# BQ76952_AFE.net
KiCad netlist of a schematic drawn in Altium Designer
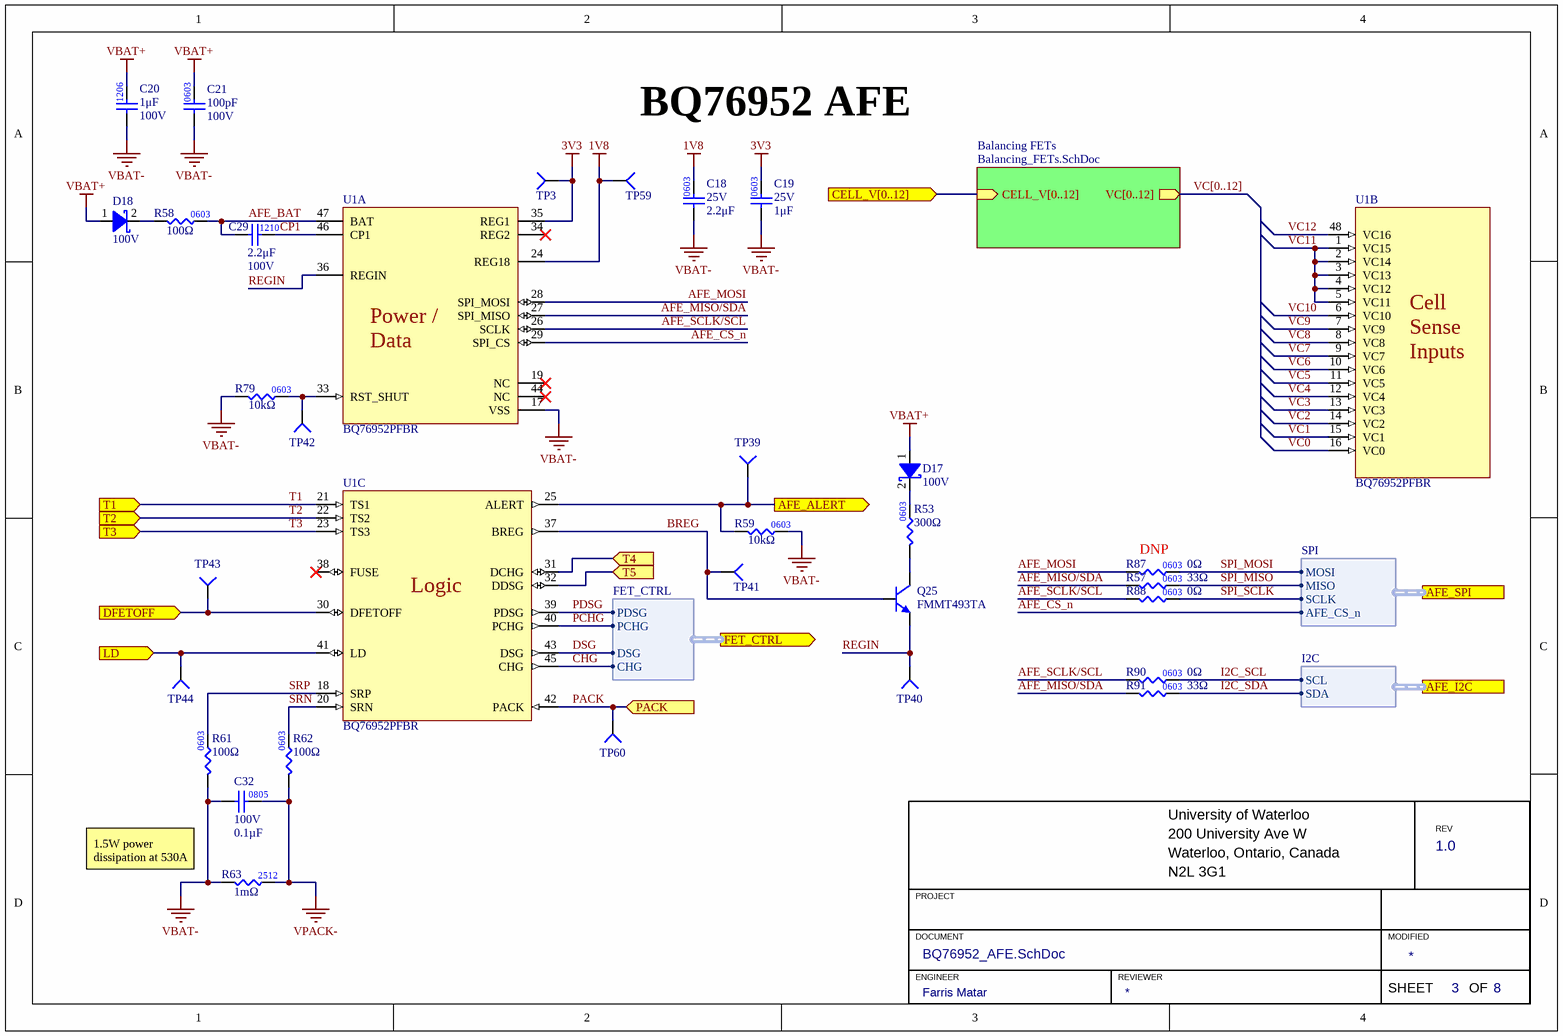
[diagram p0: BQ76952_AFE.SchDoc]

(export (version "E")
  (design (tool "Eeschema 10.0.6"))
  (components
    (comp (ref "C18")
      (value "2.2μF")
      (footprint "CAP0603")
      (description "CAP CER 2.2UF 25V X5R 0603")
      (fields (field (name "VOLTAGE RATING") "25V") (field (name "Comment") "CAP_2.2uF_25V_0603"))
      (libsource (lib "Personal_Schematic_Library_2022") (part "CAP_2.2uF_25V_0603"))
    )
    (comp (ref "C19")
      (value "1μF")
      (footprint "CAP0603")
      (description "CAP CER 1UF 25V X5R 0603")
      (fields (field (name "VOLTAGE RATING") "25V") (field (name "Comment") "CAP_1uF_25V_0603"))
      (libsource (lib "Personal_Schematic_Library_2022") (part "CAP_1uF_25V_0603"))
    )
    (comp (ref "C20")
      (value "1μF")
      (footprint "CAP1206")
      (description "CAP CER 1UF 100V X7R 1206")
      (fields (field (name "VOLTAGE RATING") "100V") (field (name "Comment") "CAP_1uF_100V_1206"))
      (libsource (lib "Personal_Schematic_Library_2022") (part "CAP_1uF_100V_1206"))
    )
    (comp (ref "C21")
      (value "100pF")
      (footprint "CAP2012")
      (description "CAP CER 100PF 100V X7R 0603")
      (fields (field (name "VOLTAGE RATING") "100V") (field (name "Comment") "CAP_100pF_100V_0603"))
      (libsource (lib "Personal_Schematic_Library_2022") (part "CAP_100pF_100V_0603"))
    )
    (comp (ref "C29")
      (value "2.2μF")
      (footprint "CAP1210")
      (description "CAP CER 2.2UF 100V X7R 1210")
      (fields (field (name "VOLTAGE RATING") "100V") (field (name "Comment") "CAP_2.2uF_100V_1210"))
      (libsource (lib "Personal_Schematic_Library_2022") (part "CAP_2.2uF_100V_1210"))
    )
    (comp (ref "C32")
      (value "0.1µF")
      (footprint "CAP0805")
      (description "CAP CER 0.1UF 100V X7R 0805")
      (fields (field (name "VOLTAGE RATING") "100V") (field (name "Comment") "CAP_0.1uF_100V_0805"))
      (libsource (lib "Personal_Schematic_Library_2022") (part "CAP_0.1uF_100V_0805"))
    )
    (comp (ref "D17")
      (value "DIO_SCHOTTKY_100V_1A")
      (footprint "SOD-123_FLAT")
      (description "DIODE SCHOTTKY 100V 1A SOD-123F")
      (fields (field (name "VR (MAX)") "100V"))
      (libsource (lib "Personal_Schematic_Library_2022") (part "DIO_SCHOTTKY_100V_1A"))
    )
    (comp (ref "D18")
      (value "DIO_SCHOTTKY_100V_1A")
      (footprint "SOD-123_FLAT")
      (description "DIODE SCHOTTKY 100V 1A SOD-123F")
      (fields (field (name "VR (MAX)") "100V"))
      (libsource (lib "Personal_Schematic_Library_2022") (part "DIO_SCHOTTKY_100V_1A"))
    )
    (comp (ref "Q25")
      (value "NPN_100V_1A")
      (footprint "SOT23-3")
      (description "TRANS NPN 100V 1A SOT23-3")
      (fields (field (name "MANUFACTURER PART NUMBER 1") "FMMT493TA"))
      (libsource (lib "Personal_Schematic_Library_2022") (part "NPN_100V_1A"))
    )
    (comp (ref "R53")
      (value "300Ω")
      (footprint "RES0603")
      (description "RES 200 OHM 1% 1/10W 0603")
      (fields (field (name "TOLERANCE") "1%") (field (name "Comment") "RES_300Ω_0603_1%"))
      (libsource (lib "Personal_Schematic_Library_2022") (part "RES_300Ω_0603_1%"))
    )
    (comp (ref "R57")
      (value "33Ω")
      (footprint "RES0603")
      (description "RES 33 OHM 1% 1/10W 0603")
      (fields (field (name "Comment") "RES_33Ω_0603_1%"))
      (libsource (lib "Personal_Schematic_Library_2022") (part "RES_33Ω_0603_1%"))
    )
    (comp (ref "R58")
      (value "100Ω")
      (footprint "RES0603")
      (description "RES 100 OHM 1% 1/10W 0603")
      (fields (field (name "Comment") "RES_100Ω_0603_1%"))
      (libsource (lib "Personal_Schematic_Library_2022") (part "RES_100Ω_0603_1%"))
    )
    (comp (ref "R59")
      (value "10kΩ")
      (footprint "RES0603")
      (description "RES 10K OHM 1% 1/8W 0603")
      (fields (field (name "Comment") "RES_10kΩ_0603_1%"))
      (libsource (lib "Personal_Schematic_Library_2022") (part "RES_10kΩ_0603_1%"))
    )
    (comp (ref "R61")
      (value "100Ω")
      (footprint "RES0603")
      (description "RES 100 OHM 1% 1/10W 0603")
      (fields (field (name "Comment") "RES_100Ω_0603_1%"))
      (libsource (lib "Personal_Schematic_Library_2022") (part "RES_100Ω_0603_1%"))
    )
    (comp (ref "R62")
      (value "100Ω")
      (footprint "RES0603")
      (description "RES 100 OHM 1% 1/10W 0603")
      (fields (field (name "Comment") "RES_100Ω_0603_1%"))
      (libsource (lib "Personal_Schematic_Library_2022") (part "RES_100Ω_0603_1%"))
    )
    (comp (ref "R63")
      (value "1mΩ")
      (footprint "RESC6532X75N")
      (description "RES 1 mOHM 1% 3W 2512")
      (fields (field (name "Comment") "RES_1mΩ_2512_1%"))
      (libsource (lib "Personal_Schematic_Library_2022") (part "RES_1mΩ_2512_1%"))
    )
    (comp (ref "R79")
      (value "10kΩ")
      (footprint "RES0603")
      (description "RES 10K OHM 1% 1/8W 0603")
      (fields (field (name "Comment") "RES_10kΩ_0603_1%"))
      (libsource (lib "Personal_Schematic_Library_2022") (part "RES_10kΩ_0603_1%"))
    )
    (comp (ref "R87")
      (value "0Ω")
      (footprint "RES0603")
      (description "RES 0 OHM JUMPER 1/10W 0603")
      (fields (field (name "Comment") "RES_0Ω_0603"))
      (libsource (lib "Personal_Schematic_Library_2022") (part "RES_0Ω_0603"))
    )
    (comp (ref "R88")
      (value "0Ω")
      (footprint "RES0603")
      (description "RES 0 OHM JUMPER 1/10W 0603")
      (fields (field (name "Comment") "RES_0Ω_0603"))
      (libsource (lib "Personal_Schematic_Library_2022") (part "RES_0Ω_0603"))
    )
    (comp (ref "R90")
      (value "0Ω")
      (footprint "RES0603")
      (description "RES 0 OHM JUMPER 1/10W 0603")
      (fields (field (name "Comment") "RES_0Ω_0603"))
      (libsource (lib "Personal_Schematic_Library_2022") (part "RES_0Ω_0603"))
    )
    (comp (ref "R91")
      (value "33Ω")
      (footprint "RES0603")
      (description "RES 33 OHM 1% 1/10W 0603")
      (fields (field (name "Comment") "RES_33Ω_0603_1%"))
      (libsource (lib "Personal_Schematic_Library_2022") (part "RES_33Ω_0603_1%"))
    )
    (comp (ref "TP3")
      (value "TESTPOINT_SMD_LOOP")
      (footprint "S1751-46R")
      (description "TESTPOINT SMD LOOP")
      (libsource (lib "UWRT_Schematic_Library_2020") (part "TESTPOINT_SMD_LOOP"))
    )
    (comp (ref "TP39")
      (value "TESTPOINT_1MM_CIRCLE")
      (footprint "TESTPOINT_CIRCLE_1MM")
      (description "TESTPOINT 1MM CIRCLE")
      (libsource (lib "Personal_Schematic_Library_2022") (part "TESTPOINT_1MM_CIRCLE"))
    )
    (comp (ref "TP40")
      (value "TESTPOINT_1MM_CIRCLE")
      (footprint "TESTPOINT_CIRCLE_1MM")
      (description "TESTPOINT 1MM CIRCLE")
      (libsource (lib "Personal_Schematic_Library_2022") (part "TESTPOINT_1MM_CIRCLE"))
    )
    (comp (ref "TP41")
      (value "TESTPOINT_1MM_CIRCLE")
      (footprint "TESTPOINT_CIRCLE_1MM")
      (description "TESTPOINT 1MM CIRCLE")
      (libsource (lib "Personal_Schematic_Library_2022") (part "TESTPOINT_1MM_CIRCLE"))
    )
    (comp (ref "TP42")
      (value "TESTPOINT_1MM_CIRCLE")
      (footprint "TESTPOINT_CIRCLE_1MM")
      (description "TESTPOINT 1MM CIRCLE")
      (libsource (lib "Personal_Schematic_Library_2022") (part "TESTPOINT_1MM_CIRCLE"))
    )
    (comp (ref "TP43")
      (value "TESTPOINT_1MM_CIRCLE")
      (footprint "TESTPOINT_CIRCLE_1MM")
      (description "TESTPOINT 1MM CIRCLE")
      (libsource (lib "Personal_Schematic_Library_2022") (part "TESTPOINT_1MM_CIRCLE"))
    )
    (comp (ref "TP44")
      (value "TESTPOINT_1MM_CIRCLE")
      (footprint "TESTPOINT_CIRCLE_1MM")
      (description "TESTPOINT 1MM CIRCLE")
      (libsource (lib "Personal_Schematic_Library_2022") (part "TESTPOINT_1MM_CIRCLE"))
    )
    (comp (ref "TP59")
      (value "TESTPOINT_1MM_SQUARE")
      (footprint "TESTPOINT_SQUARE_1MM")
      (description "TESTPOINT 1MM SQUARE")
      (libsource (lib "Personal_Schematic_Library_2022") (part "TESTPOINT_1MM_SQUARE"))
    )
    (comp (ref "TP60")
      (value "TESTPOINT_1MM_CIRCLE")
      (footprint "TESTPOINT_CIRCLE_1MM")
      (description "TESTPOINT 1MM CIRCLE")
      (libsource (lib "Personal_Schematic_Library_2022") (part "TESTPOINT_1MM_CIRCLE"))
    )
    (comp (ref "U1")
      (value "BQ76952PFBR")
      (footprint "TI_48-TQFP")
      (description "IC BAT LIFEPO4/LI-ION 3-16C TQFP")
      (libsource (lib "Personal_Schematic_Library_2022") (part "BQ7695204PFBR"))
    )
  )
  (nets
    (net (code "17") (name "/AFE_ALERT") (class "Default")
      (node (ref "R59") (pin "1") (pinfunction "1_1") (pintype "passive"))
      (node (ref "TP39") (pin "1") (pinfunction "=value_1") (pintype "passive"))
      (node (ref "U1") (pin "25") (pinfunction "ALERT_25") (pintype "output"))
    )
    (net (code "18") (name "/AFE_BAT") (class "Default")
      (node (ref "C29") (pin "1") (pinfunction "1_1") (pintype "passive"))
      (node (ref "R58") (pin "2") (pinfunction "2_2") (pintype "passive"))
      (node (ref "U1") (pin "47") (pinfunction "BAT_47") (pintype "power_in"))
    )
    (net (code "19") (name "/AFE_CS_n") (class "Default")
      (node (ref "U1") (pin "29") (pinfunction "SPI_CS_29") (pintype "bidirectional"))
    )
    (net (code "20") (name "/AFE_MISO{slash}SDA") (class "Default")
      (node (ref "R57") (pin "1") (pinfunction "1_1") (pintype "passive"))
      (node (ref "R91") (pin "1") (pinfunction "1_1") (pintype "passive"))
      (node (ref "U1") (pin "27") (pinfunction "SPI_MISO_27") (pintype "bidirectional"))
    )
    (net (code "21") (name "/AFE_MOSI") (class "Default")
      (node (ref "R87") (pin "1") (pinfunction "1_1") (pintype "passive"))
      (node (ref "U1") (pin "28") (pinfunction "SPI_MOSI_28") (pintype "bidirectional"))
    )
    (net (code "22") (name "/AFE_SCLK{slash}SCL") (class "Default")
      (node (ref "R88") (pin "1") (pinfunction "1_1") (pintype "passive"))
      (node (ref "R90") (pin "1") (pinfunction "1_1") (pintype "passive"))
      (node (ref "U1") (pin "26") (pinfunction "SCLK_26") (pintype "bidirectional"))
    )
    (net (code "23") (name "/BREG") (class "Default")
      (node (ref "Q25") (pin "1") (pinfunction "B_1") (pintype "passive"))
      (node (ref "TP41") (pin "1") (pinfunction "=value_1") (pintype "passive"))
      (node (ref "U1") (pin "37") (pinfunction "BREG_37") (pintype "output"))
    )
    (net (code "25") (name "/CHG") (class "Default")
      (node (ref "U1") (pin "45") (pinfunction "CHG_45") (pintype "output"))
    )
    (net (code "26") (name "/CP1") (class "Default")
      (node (ref "C29") (pin "2") (pinfunction "2_2") (pintype "passive"))
      (node (ref "U1") (pin "46") (pinfunction "CP1_46") (pintype "power_in"))
    )
    (net (code "27") (name "/DFETOFF") (class "Default")
      (node (ref "TP43") (pin "1") (pinfunction "=value_1") (pintype "passive"))
      (node (ref "U1") (pin "30") (pinfunction "DFETOFF_30") (pintype "bidirectional"))
    )
    (net (code "28") (name "/DSG") (class "Default")
      (node (ref "U1") (pin "43") (pinfunction "DSG_43") (pintype "output"))
    )
    (net (code "29") (name "/I2C_SCL") (class "Default")
      (node (ref "R90") (pin "2") (pinfunction "2_2") (pintype "passive"))
    )
    (net (code "30") (name "/I2C_SDA") (class "Default")
      (node (ref "R91") (pin "2") (pinfunction "2_2") (pintype "passive"))
    )
    (net (code "31") (name "/LD") (class "Default")
      (node (ref "TP44") (pin "1") (pinfunction "=value_1") (pintype "passive"))
      (node (ref "U1") (pin "41") (pinfunction "LD_41") (pintype "bidirectional"))
    )
    (net (code "32") (name "/PACK") (class "Default")
      (node (ref "TP60") (pin "1") (pinfunction "=value_1") (pintype "passive"))
      (node (ref "U1") (pin "42") (pinfunction "PACK_42") (pintype "input"))
    )
    (net (code "33") (name "/PCHG") (class "Default")
      (node (ref "U1") (pin "40") (pinfunction "PCHG_40") (pintype "output"))
    )
    (net (code "34") (name "/PDSG") (class "Default")
      (node (ref "U1") (pin "39") (pinfunction "PDSG_39") (pintype "output"))
    )
    (net (code "35") (name "/REGIN") (class "Default")
      (node (ref "Q25") (pin "2") (pinfunction "E_2") (pintype "passive"))
      (node (ref "TP40") (pin "1") (pinfunction "=value_1") (pintype "passive"))
      (node (ref "U1") (pin "36") (pinfunction "REGIN_36") (pintype "power_in"))
    )
    (net (code "36") (name "/SPI_MISO") (class "Default")
      (node (ref "R57") (pin "2") (pinfunction "2_2") (pintype "passive"))
    )
    (net (code "37") (name "/SPI_MOSI") (class "Default")
      (node (ref "R87") (pin "2") (pinfunction "2_2") (pintype "passive"))
    )
    (net (code "38") (name "/SPI_SCLK") (class "Default")
      (node (ref "R88") (pin "2") (pinfunction "2_2") (pintype "passive"))
    )
    (net (code "39") (name "/SRN") (class "Default")
      (node (ref "R62") (pin "2") (pinfunction "2_2") (pintype "passive"))
      (node (ref "U1") (pin "20") (pinfunction "SRN_20") (pintype "input"))
    )
    (net (code "40") (name "/SRP") (class "Default")
      (node (ref "R61") (pin "2") (pinfunction "2_2") (pintype "passive"))
      (node (ref "U1") (pin "18") (pinfunction "SRP_18") (pintype "input"))
    )
    (net (code "41") (name "/T1") (class "Default")
      (node (ref "U1") (pin "21") (pinfunction "TS1_21") (pintype "input"))
    )
    (net (code "42") (name "/T2") (class "Default")
      (node (ref "U1") (pin "22") (pinfunction "TS2_22") (pintype "input"))
    )
    (net (code "43") (name "/T3") (class "Default")
      (node (ref "U1") (pin "23") (pinfunction "TS3_23") (pintype "input"))
    )
    (net (code "44") (name "/T4") (class "Default")
      (node (ref "U1") (pin "31") (pinfunction "DCHG_31") (pintype "bidirectional"))
    )
    (net (code "45") (name "/T5") (class "Default")
      (node (ref "U1") (pin "32") (pinfunction "DDSG_32") (pintype "bidirectional"))
    )
    (net (code "46") (name "/VC0") (class "Default")
      (node (ref "U1") (pin "16") (pinfunction "VC0_16") (pintype "input"))
    )
    (net (code "47") (name "/VC1") (class "Default")
      (node (ref "U1") (pin "15") (pinfunction "VC1_15") (pintype "input"))
    )
    (net (code "48") (name "/VC2") (class "Default")
      (node (ref "U1") (pin "14") (pinfunction "VC2_14") (pintype "input"))
    )
    (net (code "49") (name "/VC3") (class "Default")
      (node (ref "U1") (pin "13") (pinfunction "VC3_13") (pintype "input"))
    )
    (net (code "50") (name "/VC4") (class "Default")
      (node (ref "U1") (pin "12") (pinfunction "VC4_12") (pintype "input"))
    )
    (net (code "51") (name "/VC5") (class "Default")
      (node (ref "U1") (pin "11") (pinfunction "VC5_11") (pintype "input"))
    )
    (net (code "52") (name "/VC6") (class "Default")
      (node (ref "U1") (pin "10") (pinfunction "VC6_10") (pintype "input"))
    )
    (net (code "53") (name "/VC7") (class "Default")
      (node (ref "U1") (pin "9") (pinfunction "VC7_9") (pintype "input"))
    )
    (net (code "54") (name "/VC8") (class "Default")
      (node (ref "U1") (pin "8") (pinfunction "VC8_8") (pintype "input"))
    )
    (net (code "55") (name "/VC9") (class "Default")
      (node (ref "U1") (pin "7") (pinfunction "VC9_7") (pintype "input"))
    )
    (net (code "56") (name "/VC10") (class "Default")
      (node (ref "U1") (pin "6") (pinfunction "VC10_6") (pintype "input"))
    )
    (net (code "57") (name "/VC11") (class "Default")
      (node (ref "U1") (pin "1") (pinfunction "VC15_1") (pintype "input"))
      (node (ref "U1") (pin "2") (pinfunction "VC14_2") (pintype "input"))
      (node (ref "U1") (pin "3") (pinfunction "VC13_3") (pintype "input"))
      (node (ref "U1") (pin "4") (pinfunction "VC12_4") (pintype "input"))
      (node (ref "U1") (pin "5") (pinfunction "VC11_5") (pintype "input"))
    )
    (net (code "58") (name "/VC12") (class "Default")
      (node (ref "U1") (pin "48") (pinfunction "VC16_48") (pintype "input"))
    )
    (net (code "63") (name "1V8") (class "Default")
      (node (ref "C18") (pin "2") (pinfunction "2_2") (pintype "passive"))
      (node (ref "TP59") (pin "1") (pinfunction "=value_1") (pintype "passive"))
      (node (ref "U1") (pin "24") (pinfunction "REG18_24") (pintype "power_in"))
    )
    (net (code "64") (name "3V3") (class "Default")
      (node (ref "C19") (pin "2") (pinfunction "2_2") (pintype "passive"))
      (node (ref "TP3") (pin "1") (pinfunction "=value_1") (pintype "passive"))
      (node (ref "U1") (pin "35") (pinfunction "REG1_35") (pintype "power_in"))
    )
    (net (code "65") (name "Net-(D17-Cathode)") (class "Default")
      (node (ref "D17") (pin "2") (pinfunction "Cathode_2") (pintype "passive"))
      (node (ref "R53") (pin "2") (pinfunction "2_2") (pintype "passive"))
    )
    (net (code "66") (name "Net-(D18-Cathode)") (class "Default")
      (node (ref "D18") (pin "2") (pinfunction "Cathode_2") (pintype "passive"))
      (node (ref "R58") (pin "1") (pinfunction "1_1") (pintype "passive"))
    )
    (net (code "67") (name "Net-(Q25-C)") (class "Default")
      (node (ref "Q25") (pin "3") (pinfunction "C_3") (pintype "passive"))
      (node (ref "R53") (pin "1") (pinfunction "1_1") (pintype "passive"))
    )
    (net (code "68") (name "Net-(TP42-=value)") (class "Default")
      (node (ref "R79") (pin "2") (pinfunction "2_2") (pintype "passive"))
      (node (ref "TP42") (pin "1") (pinfunction "=value_1") (pintype "passive"))
      (node (ref "U1") (pin "33") (pinfunction "RST_SHUT_33") (pintype "input"))
    )
    (net (code "69") (name "VBAT+") (class "Default")
      (node (ref "C20") (pin "2") (pinfunction "2_2") (pintype "passive"))
      (node (ref "C21") (pin "2") (pinfunction "2_2") (pintype "passive"))
      (node (ref "D17") (pin "1") (pinfunction "Anode_1") (pintype "passive"))
      (node (ref "D18") (pin "1") (pinfunction "Anode_1") (pintype "passive"))
    )
    (net (code "70") (name "VBAT-") (class "Default")
      (node (ref "C18") (pin "1") (pinfunction "1_1") (pintype "passive"))
      (node (ref "C19") (pin "1") (pinfunction "1_1") (pintype "passive"))
      (node (ref "C20") (pin "1") (pinfunction "1_1") (pintype "passive"))
      (node (ref "C21") (pin "1") (pinfunction "1_1") (pintype "passive"))
      (node (ref "C32") (pin "1") (pinfunction "1_1") (pintype "passive"))
      (node (ref "R59") (pin "2") (pinfunction "2_2") (pintype "passive"))
      (node (ref "R61") (pin "1") (pinfunction "1_1") (pintype "passive"))
      (node (ref "R63") (pin "1") (pinfunction "1_1") (pintype "passive"))
      (node (ref "R79") (pin "1") (pinfunction "1_1") (pintype "passive"))
      (node (ref "U1") (pin "17") (pinfunction "VSS_17") (pintype "power_in"))
    )
    (net (code "71") (name "VPACK-") (class "Default")
      (node (ref "C32") (pin "2") (pinfunction "2_2") (pintype "passive"))
      (node (ref "R62") (pin "1") (pinfunction "1_1") (pintype "passive"))
      (node (ref "R63") (pin "2") (pinfunction "2_2") (pintype "passive"))
    )
    (net (code "72") (name "unconnected-(U1A-NC-Pad19)") (class "Default")
      (node (ref "U1") (pin "19") (pinfunction "NC_19") (pintype "passive+no_connect"))
    )
    (net (code "73") (name "unconnected-(U1A-NC-Pad44)") (class "Default")
      (node (ref "U1") (pin "44") (pinfunction "NC_44") (pintype "passive+no_connect"))
    )
    (net (code "74") (name "unconnected-(U1A-REG2-Pad34)") (class "Default")
      (node (ref "U1") (pin "34") (pinfunction "REG2_34") (pintype "power_in+no_connect"))
    )
    (net (code "75") (name "unconnected-(U1C-FUSE-Pad38)") (class "Default")
      (node (ref "U1") (pin "38") (pinfunction "FUSE_38") (pintype "bidirectional+no_connect"))
    )
  )
)
